# Board_R1.net
KiCad netlist of a schematic drawn in EAGLE
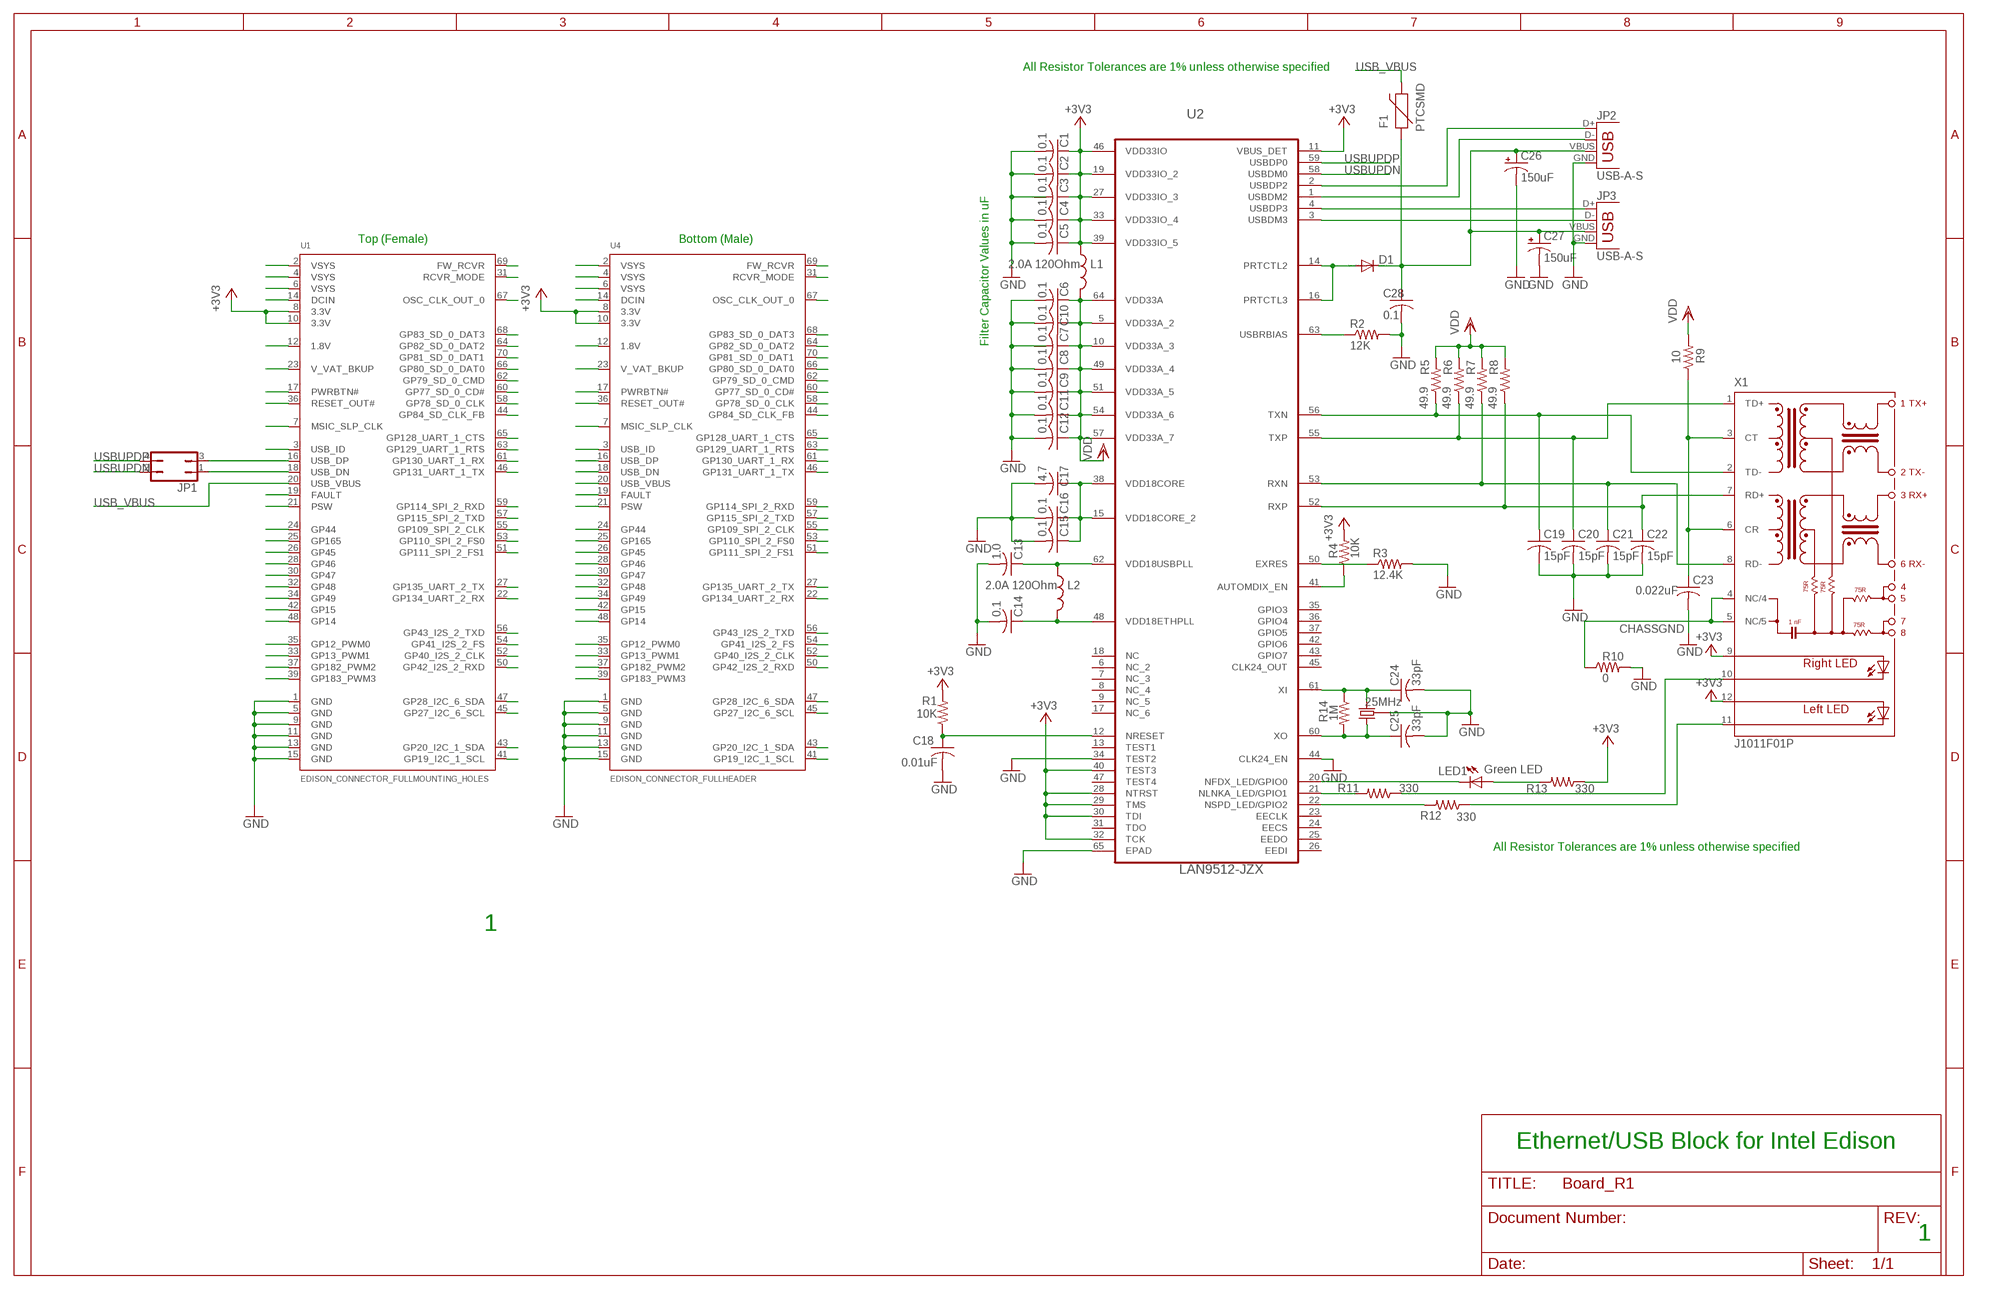
[diagram p0: schematic, sheet 1]

(export (version "E")
  (design (tool "Eeschema 10.0.6"))
  (components
    (comp (ref "C1")
      (value "0.1")
      (footprint "eagle-import:C0402K")
      (libsource (lib "eagle-import") (part "C-USC0402K"))
    )
    (comp (ref "C2")
      (value "0.1")
      (footprint "eagle-import:C0402K")
      (libsource (lib "eagle-import") (part "C-USC0402K"))
    )
    (comp (ref "C3")
      (value "0.1")
      (footprint "eagle-import:C0402K")
      (libsource (lib "eagle-import") (part "C-USC0402K"))
    )
    (comp (ref "C4")
      (value "0.1")
      (footprint "eagle-import:C0402K")
      (libsource (lib "eagle-import") (part "C-USC0402K"))
    )
    (comp (ref "C5")
      (value "0.1")
      (footprint "eagle-import:C0402K")
      (libsource (lib "eagle-import") (part "C-USC0402K"))
    )
    (comp (ref "C6")
      (value "0.1")
      (footprint "eagle-import:C0402K")
      (libsource (lib "eagle-import") (part "C-USC0402K"))
    )
    (comp (ref "C7")
      (value "0.1")
      (footprint "eagle-import:C0402K")
      (libsource (lib "eagle-import") (part "C-USC0402K"))
    )
    (comp (ref "C8")
      (value "0.1")
      (footprint "eagle-import:C0402K")
      (libsource (lib "eagle-import") (part "C-USC0402K"))
    )
    (comp (ref "C9")
      (value "0.1")
      (footprint "eagle-import:C0402K")
      (libsource (lib "eagle-import") (part "C-USC0402K"))
    )
    (comp (ref "C10")
      (value "0.1")
      (footprint "eagle-import:C0402K")
      (libsource (lib "eagle-import") (part "C-USC0402K"))
    )
    (comp (ref "C11")
      (value "0.1")
      (footprint "eagle-import:C0402K")
      (libsource (lib "eagle-import") (part "C-USC0402K"))
    )
    (comp (ref "C12")
      (value "0.1")
      (footprint "eagle-import:C0402K")
      (libsource (lib "eagle-import") (part "C-USC0402K"))
    )
    (comp (ref "C13")
      (value "1.0")
      (footprint "eagle-import:C0402K")
      (libsource (lib "eagle-import") (part "C-USC0402K"))
    )
    (comp (ref "C14")
      (value "0.1")
      (footprint "eagle-import:C0402K")
      (libsource (lib "eagle-import") (part "C-USC0402K"))
    )
    (comp (ref "C15")
      (value "0.1")
      (footprint "eagle-import:C0402K")
      (libsource (lib "eagle-import") (part "C-USC0402K"))
    )
    (comp (ref "C16")
      (value "0.1")
      (footprint "eagle-import:C0402K")
      (libsource (lib "eagle-import") (part "C-USC0402K"))
    )
    (comp (ref "C17")
      (value "4.7")
      (footprint "eagle-import:C0603K")
      (libsource (lib "eagle-import") (part "C-USC0603K"))
    )
    (comp (ref "C18")
      (value "0.01uF")
      (footprint "eagle-import:C0603K")
      (libsource (lib "eagle-import") (part "C-USC0603K"))
    )
    (comp (ref "C19")
      (value "15pF")
      (footprint "eagle-import:C0402")
      (libsource (lib "eagle-import") (part "C-USC0402"))
    )
    (comp (ref "C20")
      (value "15pF")
      (footprint "eagle-import:C0402")
      (libsource (lib "eagle-import") (part "C-USC0402"))
    )
    (comp (ref "C21")
      (value "15pF")
      (footprint "eagle-import:C0402")
      (libsource (lib "eagle-import") (part "C-USC0402"))
    )
    (comp (ref "C22")
      (value "15pF")
      (footprint "eagle-import:C0402")
      (libsource (lib "eagle-import") (part "C-USC0402"))
    )
    (comp (ref "C23")
      (value "0.022uF")
      (footprint "eagle-import:C0805")
      (libsource (lib "eagle-import") (part "resistor_C-USC0805"))
    )
    (comp (ref "C24")
      (value "33pF")
      (footprint "eagle-import:C0402")
      (libsource (lib "eagle-import") (part "C-USC0402"))
    )
    (comp (ref "C25")
      (value "33pF")
      (footprint "eagle-import:C0402")
      (libsource (lib "eagle-import") (part "C-USC0402"))
    )
    (comp (ref "C26")
      (value "150uF")
      (footprint "eagle-import:PANASONIC_E")
      (libsource (lib "eagle-import") (part "CAP_POLE"))
    )
    (comp (ref "C27")
      (value "150uF")
      (footprint "eagle-import:PANASONIC_E")
      (libsource (lib "eagle-import") (part "CAP_POLE"))
    )
    (comp (ref "C28")
      (value "0.1")
      (footprint "eagle-import:C0402K")
      (libsource (lib "eagle-import") (part "C-USC0402K"))
    )
    (comp (ref "D1")
      (value "DIODE-SOD123")
      (footprint "eagle-import:SOD123")
      (libsource (lib "eagle-import") (part "DIODE-SOD123"))
    )
    (comp (ref "F1")
      (value "PTCSMD")
      (footprint "eagle-import:PTC-1206")
      (libsource (lib "eagle-import") (part "PTCSMD"))
    )
    (comp (ref "JP1")
      (value "JP2Q")
      (footprint "eagle-import:JP2Q")
      (libsource (lib "eagle-import") (part "JP2Q"))
    )
    (comp (ref "JP2")
      (value "USB-A-S")
      (footprint "eagle-import:USB-A-S")
      (libsource (lib "eagle-import") (part "USB-A-S"))
    )
    (comp (ref "JP3")
      (value "USB-A-S")
      (footprint "eagle-import:USB-A-S")
      (libsource (lib "eagle-import") (part "USB-A-S"))
    )
    (comp (ref "L1")
      (value "2.0A 120Ohm")
      (footprint "eagle-import:L0603")
      (libsource (lib "eagle-import") (part "L-US0603"))
    )
    (comp (ref "L2")
      (value "2.0A 120Ohm")
      (footprint "eagle-import:L0603")
      (libsource (lib "eagle-import") (part "L-US0603"))
    )
    (comp (ref "LED1")
      (value "Green LED")
      (footprint "eagle-import:CHIP-LED0805")
      (libsource (lib "eagle-import") (part "LEDCHIP-LED0805"))
    )
    (comp (ref "R1")
      (value "10K")
      (footprint "eagle-import:R0603")
      (libsource (lib "eagle-import") (part "R-US_R0603"))
    )
    (comp (ref "R2")
      (value "12K")
      (footprint "eagle-import:R0603")
      (libsource (lib "eagle-import") (part "R-US_R0603"))
    )
    (comp (ref "R3")
      (value "12.4K")
      (footprint "eagle-import:R0603")
      (libsource (lib "eagle-import") (part "R-US_R0603"))
    )
    (comp (ref "R4")
      (value "10K")
      (footprint "eagle-import:R0603")
      (libsource (lib "eagle-import") (part "R-US_R0603"))
    )
    (comp (ref "R5")
      (value "49.9")
      (footprint "eagle-import:R0402")
      (libsource (lib "eagle-import") (part "R-US_R0402"))
    )
    (comp (ref "R6")
      (value "49.9")
      (footprint "eagle-import:R0402")
      (libsource (lib "eagle-import") (part "R-US_R0402"))
    )
    (comp (ref "R7")
      (value "49.9")
      (footprint "eagle-import:R0402")
      (libsource (lib "eagle-import") (part "R-US_R0402"))
    )
    (comp (ref "R8")
      (value "49.9")
      (footprint "eagle-import:R0402")
      (libsource (lib "eagle-import") (part "R-US_R0402"))
    )
    (comp (ref "R9")
      (value "10")
      (footprint "eagle-import:R0402")
      (libsource (lib "eagle-import") (part "R-US_R0402"))
    )
    (comp (ref "R10")
      (value "0")
      (footprint "eagle-import:R1210")
      (libsource (lib "eagle-import") (part "R-US_R1210"))
    )
    (comp (ref "R11")
      (value "330")
      (footprint "eagle-import:R0402")
      (libsource (lib "eagle-import") (part "R-US_R0402"))
    )
    (comp (ref "R12")
      (value "330")
      (footprint "eagle-import:R0402")
      (libsource (lib "eagle-import") (part "R-US_R0402"))
    )
    (comp (ref "R13")
      (value "330")
      (footprint "eagle-import:R0402")
      (libsource (lib "eagle-import") (part "R-US_R0402"))
    )
    (comp (ref "R14")
      (value "1M")
      (footprint "eagle-import:R0402")
      (libsource (lib "eagle-import") (part "R-US_R0402"))
    )
    (comp (ref "U$1")
      (value "25MHz")
      (footprint "eagle-import:CRYSTAL-SMD-5X3")
      (libsource (lib "eagle-import") (part "CRYSTAL-GROUNDED"))
    )
    (comp (ref "U1")
      (value "EDISON_CONNECTOR_FULLMOUNTING_HOLES")
      (footprint "eagle-import:EDISON_DAUGHTER")
      (libsource (lib "eagle-import") (part "EDISON_CONNECTOR_FULLMOUNTING_HOLES"))
    )
    (comp (ref "U2")
      (value "LAN9512-JZX")
      (footprint "eagle-import:QFN50P900X900X100-65N")
      (libsource (lib "eagle-import") (part "LAN9512-JZX"))
    )
    (comp (ref "U4")
      (value "EDISON_CONNECTOR_FULLHEADER")
      (footprint "eagle-import:DF40C-70DP-0.4(51)")
      (libsource (lib "eagle-import") (part "EDISON_CONNECTOR_FULLHEADER"))
    )
    (comp (ref "X1")
      (value "J1011F01P")
      (footprint "eagle-import:J1")
      (libsource (lib "eagle-import") (part "J1011F01P"))
    )
  )
  (nets
    (net (code "1") (name "+3V3") (class "Default")
      (node (ref "C1") (pin "1") (pinfunction "1_1") (pintype "passive"))
      (node (ref "C2") (pin "1") (pinfunction "1_1") (pintype "passive"))
      (node (ref "C3") (pin "1") (pinfunction "1_1") (pintype "passive"))
      (node (ref "C4") (pin "1") (pinfunction "1_1") (pintype "passive"))
      (node (ref "C5") (pin "1") (pinfunction "1_1") (pintype "passive"))
      (node (ref "L1") (pin "1") (pinfunction "1_1") (pintype "passive"))
      (node (ref "R1") (pin "2") (pinfunction "2_2") (pintype "passive"))
      (node (ref "R13") (pin "1") (pinfunction "1_1") (pintype "passive"))
      (node (ref "R4") (pin "2") (pinfunction "2_2") (pintype "passive"))
      (node (ref "U1") (pin "10") (pinfunction "3.3V_10") (pintype "bidirectional"))
      (node (ref "U1") (pin "8") (pinfunction "3.3V_8") (pintype "bidirectional"))
      (node (ref "U2") (pin "11") (pinfunction "VBUS_DET_11") (pintype "power_in"))
      (node (ref "U2") (pin "19") (pinfunction "VDD33IO_2_19") (pintype "power_in"))
      (node (ref "U2") (pin "27") (pinfunction "VDD33IO_3_27") (pintype "power_in"))
      (node (ref "U2") (pin "28") (pinfunction "NTRST_28") (pintype "passive"))
      (node (ref "U2") (pin "29") (pinfunction "TMS_29") (pintype "passive"))
      (node (ref "U2") (pin "30") (pinfunction "TDI_30") (pintype "passive"))
      (node (ref "U2") (pin "32") (pinfunction "TCK_32") (pintype "passive"))
      (node (ref "U2") (pin "33") (pinfunction "VDD33IO_4_33") (pintype "power_in"))
      (node (ref "U2") (pin "39") (pinfunction "VDD33IO_5_39") (pintype "power_in"))
      (node (ref "U2") (pin "40") (pinfunction "TEST3_40") (pintype "passive"))
      (node (ref "U2") (pin "46") (pinfunction "VDD33IO_46") (pintype "power_in"))
      (node (ref "U4") (pin "10") (pinfunction "3.3V_10") (pintype "bidirectional"))
      (node (ref "U4") (pin "8") (pinfunction "3.3V_8") (pintype "bidirectional"))
      (node (ref "X1") (pin "12") (pinfunction "AL_12") (pintype "passive"))
      (node (ref "X1") (pin "9") (pinfunction "A-R_9") (pintype "passive"))
    )
    (net (code "2") (name "/CHASSGND") (class "Default")
      (node (ref "R10") (pin "1") (pinfunction "1_1") (pintype "passive"))
      (node (ref "X1") (pin "4") (pinfunction "NC/4_4") (pintype "input"))
      (node (ref "X1") (pin "5") (pinfunction "NC/5_5") (pintype "input"))
    )
    (net (code "3") (name "/P2") (class "Default")
      (node (ref "U1") (pin "2") (pinfunction "VSYS_2") (pintype "bidirectional"))
      (node (ref "U4") (pin "2") (pinfunction "VSYS_2") (pintype "bidirectional"))
    )
    (net (code "4") (name "/P3") (class "Default")
      (node (ref "U1") (pin "3") (pinfunction "USB_ID_3") (pintype "bidirectional"))
      (node (ref "U4") (pin "3") (pinfunction "USB_ID_3") (pintype "bidirectional"))
    )
    (net (code "5") (name "/P4") (class "Default")
      (node (ref "U1") (pin "4") (pinfunction "VSYS_4") (pintype "bidirectional"))
      (node (ref "U4") (pin "4") (pinfunction "VSYS_4") (pintype "bidirectional"))
    )
    (net (code "6") (name "/P6") (class "Default")
      (node (ref "U1") (pin "6") (pinfunction "VSYS_6") (pintype "bidirectional"))
      (node (ref "U4") (pin "6") (pinfunction "VSYS_6") (pintype "bidirectional"))
    )
    (net (code "7") (name "/P7") (class "Default")
      (node (ref "U1") (pin "7") (pinfunction "MSIC_SLP_CLK_7") (pintype "bidirectional"))
      (node (ref "U4") (pin "7") (pinfunction "MSIC_SLP_CLK_7") (pintype "bidirectional"))
    )
    (net (code "8") (name "/P12") (class "Default")
      (node (ref "U1") (pin "12") (pinfunction "1.8V_12") (pintype "bidirectional"))
      (node (ref "U4") (pin "12") (pinfunction "1.8V_12") (pintype "bidirectional"))
    )
    (net (code "9") (name "/P14") (class "Default")
      (node (ref "U1") (pin "14") (pinfunction "DCIN_14") (pintype "bidirectional"))
      (node (ref "U4") (pin "14") (pinfunction "DCIN_14") (pintype "bidirectional"))
    )
    (net (code "10") (name "/P17") (class "Default")
      (node (ref "U1") (pin "17") (pinfunction "PWRBTN#_17") (pintype "bidirectional"))
      (node (ref "U4") (pin "17") (pinfunction "PWRBTN#_17") (pintype "bidirectional"))
    )
    (net (code "11") (name "/P19") (class "Default")
      (node (ref "U1") (pin "19") (pinfunction "FAULT_19") (pintype "bidirectional"))
      (node (ref "U4") (pin "19") (pinfunction "FAULT_19") (pintype "bidirectional"))
    )
    (net (code "12") (name "/P21") (class "Default")
      (node (ref "U1") (pin "21") (pinfunction "PSW_21") (pintype "bidirectional"))
      (node (ref "U4") (pin "21") (pinfunction "PSW_21") (pintype "bidirectional"))
    )
    (net (code "13") (name "/P22") (class "Default")
      (node (ref "U1") (pin "22") (pinfunction "GP134_UART_2_RX_22") (pintype "bidirectional"))
      (node (ref "U4") (pin "22") (pinfunction "GP134_UART_2_RX_22") (pintype "bidirectional"))
    )
    (net (code "14") (name "/P23") (class "Default")
      (node (ref "U1") (pin "23") (pinfunction "V_VAT_BKUP_23") (pintype "bidirectional"))
      (node (ref "U4") (pin "23") (pinfunction "V_VAT_BKUP_23") (pintype "bidirectional"))
    )
    (net (code "15") (name "/P24") (class "Default")
      (node (ref "U1") (pin "24") (pinfunction "GP44_24") (pintype "bidirectional"))
      (node (ref "U4") (pin "24") (pinfunction "GP44_24") (pintype "bidirectional"))
    )
    (net (code "16") (name "/P25") (class "Default")
      (node (ref "U1") (pin "25") (pinfunction "GP165_25") (pintype "bidirectional"))
      (node (ref "U4") (pin "25") (pinfunction "GP165_25") (pintype "bidirectional"))
    )
    (net (code "17") (name "/P26") (class "Default")
      (node (ref "U1") (pin "26") (pinfunction "GP45_26") (pintype "bidirectional"))
      (node (ref "U4") (pin "26") (pinfunction "GP45_26") (pintype "bidirectional"))
    )
    (net (code "18") (name "/P27") (class "Default")
      (node (ref "U1") (pin "27") (pinfunction "GP135_UART_2_TX_27") (pintype "bidirectional"))
      (node (ref "U4") (pin "27") (pinfunction "GP135_UART_2_TX_27") (pintype "bidirectional"))
    )
    (net (code "19") (name "/P28") (class "Default")
      (node (ref "U1") (pin "28") (pinfunction "GP46_28") (pintype "bidirectional"))
      (node (ref "U4") (pin "28") (pinfunction "GP46_28") (pintype "bidirectional"))
    )
    (net (code "20") (name "/P30") (class "Default")
      (node (ref "U1") (pin "30") (pinfunction "GP47_30") (pintype "bidirectional"))
      (node (ref "U4") (pin "30") (pinfunction "GP47_30") (pintype "bidirectional"))
    )
    (net (code "21") (name "/P31") (class "Default")
      (node (ref "U1") (pin "31") (pinfunction "RCVR_MODE_31") (pintype "bidirectional"))
      (node (ref "U4") (pin "31") (pinfunction "RCVR_MODE_31") (pintype "bidirectional"))
    )
    (net (code "22") (name "/P32") (class "Default")
      (node (ref "U1") (pin "32") (pinfunction "GP48_32") (pintype "bidirectional"))
      (node (ref "U4") (pin "32") (pinfunction "GP48_32") (pintype "bidirectional"))
    )
    (net (code "23") (name "/P33") (class "Default")
      (node (ref "U1") (pin "33") (pinfunction "GP13_PWM1_33") (pintype "bidirectional"))
      (node (ref "U4") (pin "33") (pinfunction "GP13_PWM1_33") (pintype "bidirectional"))
    )
    (net (code "24") (name "/P34") (class "Default")
      (node (ref "U1") (pin "34") (pinfunction "GP49_34") (pintype "bidirectional"))
      (node (ref "U4") (pin "34") (pinfunction "GP49_34") (pintype "bidirectional"))
    )
    (net (code "25") (name "/P35") (class "Default")
      (node (ref "U1") (pin "35") (pinfunction "GP12_PWM0_35") (pintype "bidirectional"))
      (node (ref "U4") (pin "35") (pinfunction "GP12_PWM0_35") (pintype "bidirectional"))
    )
    (net (code "26") (name "/P36") (class "Default")
      (node (ref "U1") (pin "36") (pinfunction "RESET_OUT#_36") (pintype "bidirectional"))
      (node (ref "U4") (pin "36") (pinfunction "RESET_OUT#_36") (pintype "bidirectional"))
    )
    (net (code "27") (name "/P37") (class "Default")
      (node (ref "U1") (pin "37") (pinfunction "GP182_PWM2_37") (pintype "bidirectional"))
      (node (ref "U4") (pin "37") (pinfunction "GP182_PWM2_37") (pintype "bidirectional"))
    )
    (net (code "28") (name "/P39") (class "Default")
      (node (ref "U1") (pin "39") (pinfunction "GP183_PWM3_39") (pintype "bidirectional"))
      (node (ref "U4") (pin "39") (pinfunction "GP183_PWM3_39") (pintype "bidirectional"))
    )
    (net (code "29") (name "/P41") (class "Default")
      (node (ref "U1") (pin "41") (pinfunction "GP19_I2C_1_SCL_41") (pintype "bidirectional"))
      (node (ref "U4") (pin "41") (pinfunction "GP19_I2C_1_SCL_41") (pintype "bidirectional"))
    )
    (net (code "30") (name "/P42") (class "Default")
      (node (ref "U1") (pin "42") (pinfunction "GP15_42") (pintype "bidirectional"))
      (node (ref "U4") (pin "42") (pinfunction "GP15_42") (pintype "bidirectional"))
    )
    (net (code "31") (name "/P43") (class "Default")
      (node (ref "U1") (pin "43") (pinfunction "GP20_I2C_1_SDA_43") (pintype "bidirectional"))
      (node (ref "U4") (pin "43") (pinfunction "GP20_I2C_1_SDA_43") (pintype "bidirectional"))
    )
    (net (code "32") (name "/P44") (class "Default")
      (node (ref "U1") (pin "44") (pinfunction "GP84_SD_CLK_FB_44") (pintype "bidirectional"))
      (node (ref "U4") (pin "44") (pinfunction "GP84_SD_CLK_FB_44") (pintype "bidirectional"))
    )
    (net (code "33") (name "/P45") (class "Default")
      (node (ref "U1") (pin "45") (pinfunction "GP27_I2C_6_SCL_45") (pintype "bidirectional"))
      (node (ref "U4") (pin "45") (pinfunction "GP27_I2C_6_SCL_45") (pintype "bidirectional"))
    )
    (net (code "34") (name "/P46") (class "Default")
      (node (ref "U1") (pin "46") (pinfunction "GP131_UART_1_TX_46") (pintype "bidirectional"))
      (node (ref "U4") (pin "46") (pinfunction "GP131_UART_1_TX_46") (pintype "bidirectional"))
    )
    (net (code "35") (name "/P47") (class "Default")
      (node (ref "U1") (pin "47") (pinfunction "GP28_I2C_6_SDA_47") (pintype "bidirectional"))
      (node (ref "U4") (pin "47") (pinfunction "GP28_I2C_6_SDA_47") (pintype "bidirectional"))
    )
    (net (code "36") (name "/P48") (class "Default")
      (node (ref "U1") (pin "48") (pinfunction "GP14_48") (pintype "bidirectional"))
      (node (ref "U4") (pin "48") (pinfunction "GP14_48") (pintype "bidirectional"))
    )
    (net (code "37") (name "/P50") (class "Default")
      (node (ref "U1") (pin "50") (pinfunction "GP42_I2S_2_RXD_50") (pintype "bidirectional"))
      (node (ref "U4") (pin "50") (pinfunction "GP42_I2S_2_RXD_50") (pintype "bidirectional"))
    )
    (net (code "38") (name "/P51") (class "Default")
      (node (ref "U1") (pin "51") (pinfunction "GP111_SPI_2_FS1_51") (pintype "bidirectional"))
      (node (ref "U4") (pin "51") (pinfunction "GP111_SPI_2_FS1_51") (pintype "bidirectional"))
    )
    (net (code "39") (name "/P52") (class "Default")
      (node (ref "U1") (pin "52") (pinfunction "GP40_I2S_2_CLK_52") (pintype "bidirectional"))
      (node (ref "U4") (pin "52") (pinfunction "GP40_I2S_2_CLK_52") (pintype "bidirectional"))
    )
    (net (code "40") (name "/P53") (class "Default")
      (node (ref "U1") (pin "53") (pinfunction "GP110_SPI_2_FS0_53") (pintype "bidirectional"))
      (node (ref "U4") (pin "53") (pinfunction "GP110_SPI_2_FS0_53") (pintype "bidirectional"))
    )
    (net (code "41") (name "/P54") (class "Default")
      (node (ref "U1") (pin "54") (pinfunction "GP41_I2S_2_FS_54") (pintype "bidirectional"))
      (node (ref "U4") (pin "54") (pinfunction "GP41_I2S_2_FS_54") (pintype "bidirectional"))
    )
    (net (code "42") (name "/P55") (class "Default")
      (node (ref "U1") (pin "55") (pinfunction "GP109_SPI_2_CLK_55") (pintype "bidirectional"))
      (node (ref "U4") (pin "55") (pinfunction "GP109_SPI_2_CLK_55") (pintype "bidirectional"))
    )
    (net (code "43") (name "/P56") (class "Default")
      (node (ref "U1") (pin "56") (pinfunction "GP43_I2S_2_TXD_56") (pintype "bidirectional"))
      (node (ref "U4") (pin "56") (pinfunction "GP43_I2S_2_TXD_56") (pintype "bidirectional"))
    )
    (net (code "44") (name "/P57") (class "Default")
      (node (ref "U1") (pin "57") (pinfunction "GP115_SPI_2_TXD_57") (pintype "bidirectional"))
      (node (ref "U4") (pin "57") (pinfunction "GP115_SPI_2_TXD_57") (pintype "bidirectional"))
    )
    (net (code "45") (name "/P58") (class "Default")
      (node (ref "U1") (pin "58") (pinfunction "GP78_SD_0_CLK_58") (pintype "bidirectional"))
      (node (ref "U4") (pin "58") (pinfunction "GP78_SD_0_CLK_58") (pintype "bidirectional"))
    )
    (net (code "46") (name "/P59") (class "Default")
      (node (ref "U1") (pin "59") (pinfunction "GP114_SPI_2_RXD_59") (pintype "bidirectional"))
      (node (ref "U4") (pin "59") (pinfunction "GP114_SPI_2_RXD_59") (pintype "bidirectional"))
    )
    (net (code "47") (name "/P60") (class "Default")
      (node (ref "U1") (pin "60") (pinfunction "GP77_SD_0_CD#_60") (pintype "bidirectional"))
      (node (ref "U4") (pin "60") (pinfunction "GP77_SD_0_CD#_60") (pintype "bidirectional"))
    )
    (net (code "48") (name "/P61") (class "Default")
      (node (ref "U1") (pin "61") (pinfunction "GP130_UART_1_RX_61") (pintype "bidirectional"))
      (node (ref "U4") (pin "61") (pinfunction "GP130_UART_1_RX_61") (pintype "bidirectional"))
    )
    (net (code "49") (name "/P62") (class "Default")
      (node (ref "U1") (pin "62") (pinfunction "GP79_SD_0_CMD_62") (pintype "bidirectional"))
      (node (ref "U4") (pin "62") (pinfunction "GP79_SD_0_CMD_62") (pintype "bidirectional"))
    )
    (net (code "50") (name "/P63") (class "Default")
      (node (ref "U1") (pin "63") (pinfunction "GP129_UART_1_RTS_63") (pintype "bidirectional"))
      (node (ref "U4") (pin "63") (pinfunction "GP129_UART_1_RTS_63") (pintype "bidirectional"))
    )
    (net (code "51") (name "/P64") (class "Default")
      (node (ref "U1") (pin "64") (pinfunction "GP82_SD_0_DAT2_64") (pintype "bidirectional"))
      (node (ref "U4") (pin "64") (pinfunction "GP82_SD_0_DAT2_64") (pintype "bidirectional"))
    )
    (net (code "52") (name "/P65") (class "Default")
      (node (ref "U1") (pin "65") (pinfunction "GP128_UART_1_CTS_65") (pintype "bidirectional"))
      (node (ref "U4") (pin "65") (pinfunction "GP128_UART_1_CTS_65") (pintype "bidirectional"))
    )
    (net (code "53") (name "/P66") (class "Default")
      (node (ref "U1") (pin "66") (pinfunction "GP80_SD_0_DAT0_66") (pintype "bidirectional"))
      (node (ref "U4") (pin "66") (pinfunction "GP80_SD_0_DAT0_66") (pintype "bidirectional"))
    )
    (net (code "54") (name "/P67") (class "Default")
      (node (ref "U1") (pin "67") (pinfunction "OSC_CLK_OUT_0_67") (pintype "bidirectional"))
      (node (ref "U4") (pin "67") (pinfunction "OSC_CLK_OUT_0_67") (pintype "bidirectional"))
    )
    (net (code "55") (name "/P68") (class "Default")
      (node (ref "U1") (pin "68") (pinfunction "GP83_SD_0_DAT3_68") (pintype "bidirectional"))
      (node (ref "U4") (pin "68") (pinfunction "GP83_SD_0_DAT3_68") (pintype "bidirectional"))
    )
    (net (code "56") (name "/P69") (class "Default")
      (node (ref "U1") (pin "69") (pinfunction "FW_RCVR_69") (pintype "bidirectional"))
      (node (ref "U4") (pin "69") (pinfunction "FW_RCVR_69") (pintype "bidirectional"))
    )
    (net (code "57") (name "/P70") (class "Default")
      (node (ref "U1") (pin "70") (pinfunction "GP81_SD_0_DAT1_70") (pintype "bidirectional"))
      (node (ref "U4") (pin "70") (pinfunction "GP81_SD_0_DAT1_70") (pintype "bidirectional"))
    )
    (net (code "58") (name "/USBUP") (class "Default")
      (node (ref "JP1") (pin "3") (pinfunction "3_3") (pintype "passive"))
      (node (ref "U1") (pin "16") (pinfunction "USB_DP_16") (pintype "bidirectional"))
      (node (ref "U4") (pin "16") (pinfunction "USB_DP_16") (pintype "bidirectional"))
    )
    (net (code "59") (name "/USBUP2") (class "Default")
      (node (ref "JP1") (pin "1") (pinfunction "1_1") (pintype "passive"))
      (node (ref "U1") (pin "18") (pinfunction "USB_DN_18") (pintype "bidirectional"))
      (node (ref "U4") (pin "18") (pinfunction "USB_DN_18") (pintype "bidirectional"))
    )
    (net (code "60") (name "/USBUPDN") (class "Default")
      (node (ref "JP1") (pin "2") (pinfunction "2_2") (pintype "passive"))
      (node (ref "U2") (pin "58") (pinfunction "USBDM0_58") (pintype "passive"))
    )
    (net (code "61") (name "/USBUPDP") (class "Default")
      (node (ref "JP1") (pin "4") (pinfunction "4_4") (pintype "passive"))
      (node (ref "U2") (pin "59") (pinfunction "USBDP0_59") (pintype "passive"))
    )
    (net (code "62") (name "/USB_VBUS") (class "Default")
      (node (ref "F1") (pin "2") (pinfunction "2_2") (pintype "bidirectional"))
      (node (ref "U1") (pin "20") (pinfunction "USB_VBUS_20") (pintype "bidirectional"))
      (node (ref "U4") (pin "20") (pinfunction "USB_VBUS_20") (pintype "bidirectional"))
    )
    (net (code "63") (name "GND") (class "Default")
      (node (ref "C1") (pin "2") (pinfunction "2_2") (pintype "passive"))
      (node (ref "C10") (pin "2") (pinfunction "2_2") (pintype "passive"))
      (node (ref "C11") (pin "2") (pinfunction "2_2") (pintype "passive"))
      (node (ref "C12") (pin "2") (pinfunction "2_2") (pintype "passive"))
      (node (ref "C13") (pin "2") (pinfunction "2_2") (pintype "passive"))
      (node (ref "C14") (pin "2") (pinfunction "2_2") (pintype "passive"))
      (node (ref "C15") (pin "2") (pinfunction "2_2") (pintype "passive"))
      (node (ref "C16") (pin "2") (pinfunction "2_2") (pintype "passive"))
      (node (ref "C17") (pin "2") (pinfunction "2_2") (pintype "passive"))
      (node (ref "C18") (pin "2") (pinfunction "2_2") (pintype "passive"))
      (node (ref "C19") (pin "2") (pinfunction "2_2") (pintype "passive"))
      (node (ref "C2") (pin "2") (pinfunction "2_2") (pintype "passive"))
      (node (ref "C20") (pin "2") (pinfunction "2_2") (pintype "passive"))
      (node (ref "C21") (pin "2") (pinfunction "2_2") (pintype "passive"))
      (node (ref "C22") (pin "2") (pinfunction "2_2") (pintype "passive"))
      (node (ref "C23") (pin "2") (pinfunction "2_2") (pintype "passive"))
      (node (ref "C24") (pin "2") (pinfunction "2_2") (pintype "passive"))
      (node (ref "C25") (pin "2") (pinfunction "2_2") (pintype "passive"))
      (node (ref "C26") (pin "-") (pinfunction "-_-") (pintype "passive"))
      (node (ref "C27") (pin "-") (pinfunction "-_-") (pintype "passive"))
      (node (ref "C28") (pin "2") (pinfunction "2_2") (pintype "passive"))
      (node (ref "C3") (pin "2") (pinfunction "2_2") (pintype "passive"))
      (node (ref "C4") (pin "2") (pinfunction "2_2") (pintype "passive"))
      (node (ref "C5") (pin "2") (pinfunction "2_2") (pintype "passive"))
      (node (ref "C6") (pin "2") (pinfunction "2_2") (pintype "passive"))
      (node (ref "C7") (pin "2") (pinfunction "2_2") (pintype "passive"))
      (node (ref "C8") (pin "2") (pinfunction "2_2") (pintype "passive"))
      (node (ref "C9") (pin "2") (pinfunction "2_2") (pintype "passive"))
      (node (ref "JP2") (pin "GND") (pinfunction "GND_GND") (pintype "bidirectional"))
      (node (ref "JP3") (pin "GND") (pinfunction "GND_GND") (pintype "bidirectional"))
      (node (ref "R10") (pin "2") (pinfunction "2_2") (pintype "passive"))
      (node (ref "R2") (pin "2") (pinfunction "2_2") (pintype "passive"))
      (node (ref "R3") (pin "2") (pinfunction "2_2") (pintype "passive"))
      (node (ref "U$1") (pin "2") (pinfunction "3_2") (pintype "passive"))
      (node (ref "U$1") (pin "4") (pinfunction "3_4") (pintype "passive"))
      (node (ref "U1") (pin "1") (pinfunction "GND_1") (pintype "bidirectional"))
      (node (ref "U1") (pin "11") (pinfunction "GND_11") (pintype "bidirectional"))
      (node (ref "U1") (pin "13") (pinfunction "GND_13") (pintype "bidirectional"))
      (node (ref "U1") (pin "15") (pinfunction "GND_15") (pintype "bidirectional"))
      (node (ref "U1") (pin "5") (pinfunction "GND_5") (pintype "bidirectional"))
      (node (ref "U1") (pin "9") (pinfunction "GND_9") (pintype "bidirectional"))
      (node (ref "U2") (pin "34") (pinfunction "TEST2_34") (pintype "passive"))
      (node (ref "U2") (pin "44") (pinfunction "CLK24_EN_44") (pintype "passive"))
      (node (ref "U2") (pin "65") (pinfunction "EPAD_65") (pintype "passive"))
      (node (ref "U4") (pin "1") (pinfunction "GND_1") (pintype "bidirectional"))
      (node (ref "U4") (pin "11") (pinfunction "GND_11") (pintype "bidirectional"))
      (node (ref "U4") (pin "13") (pinfunction "GND_13") (pintype "bidirectional"))
      (node (ref "U4") (pin "15") (pinfunction "GND_15") (pintype "bidirectional"))
      (node (ref "U4") (pin "5") (pinfunction "GND_5") (pintype "bidirectional"))
      (node (ref "U4") (pin "9") (pinfunction "GND_9") (pintype "bidirectional"))
    )
    (net (code "64") (name "Net-(C26-Pad+)") (class "Default")
      (node (ref "C26") (pin "+") (pinfunction "+_+") (pintype "passive"))
      (node (ref "C27") (pin "+") (pinfunction "+_+") (pintype "passive"))
      (node (ref "C28") (pin "1") (pinfunction "1_1") (pintype "passive"))
      (node (ref "D1") (pin "C") (pinfunction "C_C") (pintype "passive"))
      (node (ref "F1") (pin "1") (pinfunction "1_1") (pintype "bidirectional"))
      (node (ref "JP2") (pin "VBUS") (pinfunction "VBUS_VBUS") (pintype "bidirectional"))
      (node (ref "JP3") (pin "VBUS") (pinfunction "VBUS_VBUS") (pintype "bidirectional"))
    )
    (net (code "65") (name "Net-(LED1-PadA)") (class "Default")
      (node (ref "LED1") (pin "A") (pinfunction "A_A") (pintype "passive"))
      (node (ref "R13") (pin "2") (pinfunction "2_2") (pintype "passive"))
    )
    (net (code "66") (name "Net-(U$1-1)") (class "Default")
      (node (ref "C25") (pin "1") (pinfunction "1_1") (pintype "passive"))
      (node (ref "R14") (pin "2") (pinfunction "2_2") (pintype "passive"))
      (node (ref "U$1") (pin "3") (pinfunction "1_3") (pintype "passive"))
      (node (ref "U2") (pin "60") (pinfunction "XO_60") (pintype "passive"))
    )
    (net (code "67") (name "Net-(U$1-2)") (class "Default")
      (node (ref "C24") (pin "1") (pinfunction "1_1") (pintype "passive"))
      (node (ref "R14") (pin "1") (pinfunction "1_1") (pintype "passive"))
      (node (ref "U$1") (pin "1") (pinfunction "2_1") (pintype "passive"))
      (node (ref "U2") (pin "61") (pinfunction "XI_61") (pintype "passive"))
    )
    (net (code "68") (name "Net-(U2-AUTOMDIX_EN)") (class "Default")
      (node (ref "R4") (pin "1") (pinfunction "1_1") (pintype "passive"))
      (node (ref "U2") (pin "41") (pinfunction "AUTOMDIX_EN_41") (pintype "passive"))
    )
    (net (code "69") (name "Net-(U2-EXRES)") (class "Default")
      (node (ref "R3") (pin "1") (pinfunction "1_1") (pintype "passive"))
      (node (ref "U2") (pin "50") (pinfunction "EXRES_50") (pintype "passive"))
    )
    (net (code "70") (name "Net-(U2-NFDX_LED{slash}GPIO0)") (class "Default")
      (node (ref "LED1") (pin "C") (pinfunction "C_C") (pintype "passive"))
      (node (ref "U2") (pin "20") (pinfunction "NFDX_LED/GPIO0_20") (pintype "bidirectional"))
    )
    (net (code "71") (name "Net-(U2-NLNKA_LED{slash}GPIO1)") (class "Default")
      (node (ref "R11") (pin "2") (pinfunction "2_2") (pintype "passive"))
      (node (ref "U2") (pin "21") (pinfunction "NLNKA_LED/GPIO1_21") (pintype "bidirectional"))
    )
    (net (code "72") (name "Net-(U2-NRESET)") (class "Default")
      (node (ref "C18") (pin "1") (pinfunction "1_1") (pintype "passive"))
      (node (ref "R1") (pin "1") (pinfunction "1_1") (pintype "passive"))
      (node (ref "U2") (pin "12") (pinfunction "NRESET_12") (pintype "passive"))
    )
    (net (code "73") (name "Net-(U2-NSPD_LED{slash}GPIO2)") (class "Default")
      (node (ref "R12") (pin "2") (pinfunction "2_2") (pintype "passive"))
      (node (ref "U2") (pin "22") (pinfunction "NSPD_LED/GPIO2_22") (pintype "bidirectional"))
    )
    (net (code "74") (name "Net-(U2-PRTCTL2)") (class "Default")
      (node (ref "D1") (pin "A") (pinfunction "A_A") (pintype "passive"))
      (node (ref "U2") (pin "14") (pinfunction "PRTCTL2_14") (pintype "passive"))
      (node (ref "U2") (pin "16") (pinfunction "PRTCTL3_16") (pintype "passive"))
    )
    (net (code "75") (name "Net-(U2-RXN)") (class "Default")
      (node (ref "C21") (pin "1") (pinfunction "1_1") (pintype "passive"))
      (node (ref "R7") (pin "1") (pinfunction "1_1") (pintype "passive"))
      (node (ref "U2") (pin "53") (pinfunction "RXN_53") (pintype "passive"))
      (node (ref "X1") (pin "8") (pinfunction "RD-_8") (pintype "input"))
    )
    (net (code "76") (name "Net-(U2-RXP)") (class "Default")
      (node (ref "C22") (pin "1") (pinfunction "1_1") (pintype "passive"))
      (node (ref "R8") (pin "1") (pinfunction "1_1") (pintype "passive"))
      (node (ref "U2") (pin "52") (pinfunction "RXP_52") (pintype "passive"))
      (node (ref "X1") (pin "7") (pinfunction "RD+_7") (pintype "input"))
    )
    (net (code "77") (name "Net-(U2-TXN)") (class "Default")
      (node (ref "C19") (pin "1") (pinfunction "1_1") (pintype "passive"))
      (node (ref "R5") (pin "1") (pinfunction "1_1") (pintype "passive"))
      (node (ref "U2") (pin "56") (pinfunction "TXN_56") (pintype "passive"))
      (node (ref "X1") (pin "2") (pinfunction "TD-_2") (pintype "input"))
    )
    (net (code "78") (name "Net-(U2-TXP)") (class "Default")
      (node (ref "C20") (pin "1") (pinfunction "1_1") (pintype "passive"))
      (node (ref "R6") (pin "1") (pinfunction "1_1") (pintype "passive"))
      (node (ref "U2") (pin "55") (pinfunction "TXP_55") (pintype "passive"))
      (node (ref "X1") (pin "1") (pinfunction "TD+_1") (pintype "input"))
    )
    (net (code "79") (name "Net-(U2-USBDM2)") (class "Default")
      (node (ref "JP2") (pin "D-") (pinfunction "D-_D-") (pintype "bidirectional"))
      (node (ref "U2") (pin "1") (pinfunction "USBDM2_1") (pintype "passive"))
    )
    (net (code "80") (name "Net-(U2-USBDM3)") (class "Default")
      (node (ref "JP3") (pin "D-") (pinfunction "D-_D-") (pintype "bidirectional"))
      (node (ref "U2") (pin "3") (pinfunction "USBDM3_3") (pintype "passive"))
    )
    (net (code "81") (name "Net-(U2-USBDP2)") (class "Default")
      (node (ref "JP2") (pin "D+") (pinfunction "D+_D+") (pintype "bidirectional"))
      (node (ref "U2") (pin "2") (pinfunction "USBDP2_2") (pintype "passive"))
    )
    (net (code "82") (name "Net-(U2-USBDP3)") (class "Default")
      (node (ref "JP3") (pin "D+") (pinfunction "D+_D+") (pintype "bidirectional"))
      (node (ref "U2") (pin "4") (pinfunction "USBDP3_4") (pintype "passive"))
    )
    (net (code "83") (name "Net-(U2-USBRBIAS)") (class "Default")
      (node (ref "R2") (pin "1") (pinfunction "1_1") (pintype "passive"))
      (node (ref "U2") (pin "63") (pinfunction "USBRBIAS_63") (pintype "passive"))
    )
    (net (code "84") (name "Net-(U2-VDD18CORE)") (class "Default")
      (node (ref "C15") (pin "1") (pinfunction "1_1") (pintype "passive"))
      (node (ref "C16") (pin "1") (pinfunction "1_1") (pintype "passive"))
      (node (ref "C17") (pin "1") (pinfunction "1_1") (pintype "passive"))
      (node (ref "U2") (pin "15") (pinfunction "VDD18CORE_2_15") (pintype "power_in"))
      (node (ref "U2") (pin "38") (pinfunction "VDD18CORE_38") (pintype "power_in"))
    )
    (net (code "85") (name "Net-(U2-VDD18ETHPLL)") (class "Default")
      (node (ref "C14") (pin "1") (pinfunction "1_1") (pintype "passive"))
      (node (ref "L2") (pin "2") (pinfunction "2_2") (pintype "passive"))
      (node (ref "U2") (pin "48") (pinfunction "VDD18ETHPLL_48") (pintype "power_in"))
    )
    (net (code "86") (name "Net-(U2-VDD18USBPLL)") (class "Default")
      (node (ref "C13") (pin "1") (pinfunction "1_1") (pintype "passive"))
      (node (ref "L2") (pin "1") (pinfunction "1_1") (pintype "passive"))
      (node (ref "U2") (pin "62") (pinfunction "VDD18USBPLL_62") (pintype "power_in"))
    )
    (net (code "87") (name "Net-(X1-C-L)") (class "Default")
      (node (ref "R12") (pin "1") (pinfunction "1_1") (pintype "passive"))
      (node (ref "X1") (pin "11") (pinfunction "C-L_11") (pintype "passive"))
    )
    (net (code "88") (name "Net-(X1-C-R)") (class "Default")
      (node (ref "R11") (pin "1") (pinfunction "1_1") (pintype "passive"))
      (node (ref "X1") (pin "10") (pinfunction "C-R_10") (pintype "passive"))
    )
    (net (code "89") (name "Net-(X1-CR)") (class "Default")
      (node (ref "C23") (pin "1") (pinfunction "1_1") (pintype "passive"))
      (node (ref "R9") (pin "1") (pinfunction "1_1") (pintype "passive"))
      (node (ref "X1") (pin "3") (pinfunction "CT_3") (pintype "input"))
      (node (ref "X1") (pin "6") (pinfunction "CR_6") (pintype "input"))
    )
    (net (code "90") (name "VDD") (class "Default")
      (node (ref "C10") (pin "1") (pinfunction "1_1") (pintype "passive"))
      (node (ref "C11") (pin "1") (pinfunction "1_1") (pintype "passive"))
      (node (ref "C12") (pin "1") (pinfunction "1_1") (pintype "passive"))
      (node (ref "C6") (pin "1") (pinfunction "1_1") (pintype "passive"))
      (node (ref "C7") (pin "1") (pinfunction "1_1") (pintype "passive"))
      (node (ref "C8") (pin "1") (pinfunction "1_1") (pintype "passive"))
      (node (ref "C9") (pin "1") (pinfunction "1_1") (pintype "passive"))
      (node (ref "L1") (pin "2") (pinfunction "2_2") (pintype "passive"))
      (node (ref "R5") (pin "2") (pinfunction "2_2") (pintype "passive"))
      (node (ref "R6") (pin "2") (pinfunction "2_2") (pintype "passive"))
      (node (ref "R7") (pin "2") (pinfunction "2_2") (pintype "passive"))
      (node (ref "R8") (pin "2") (pinfunction "2_2") (pintype "passive"))
      (node (ref "R9") (pin "2") (pinfunction "2_2") (pintype "passive"))
      (node (ref "U2") (pin "10") (pinfunction "VDD33A_3_10") (pintype "power_in"))
      (node (ref "U2") (pin "49") (pinfunction "VDD33A_4_49") (pintype "power_in"))
      (node (ref "U2") (pin "5") (pinfunction "VDD33A_2_5") (pintype "power_in"))
      (node (ref "U2") (pin "51") (pinfunction "VDD33A_5_51") (pintype "power_in"))
      (node (ref "U2") (pin "54") (pinfunction "VDD33A_6_54") (pintype "power_in"))
      (node (ref "U2") (pin "57") (pinfunction "VDD33A_7_57") (pintype "power_in"))
      (node (ref "U2") (pin "64") (pinfunction "VDD33A_64") (pintype "power_in"))
    )
    (net (code "91") (name "unconnected-(U2-CLK24_OUT-Pad45)") (class "Default")
      (node (ref "U2") (pin "45") (pinfunction "CLK24_OUT_45") (pintype "passive"))
    )
    (net (code "92") (name "unconnected-(U2-EECLK-Pad23)") (class "Default")
      (node (ref "U2") (pin "23") (pinfunction "EECLK_23") (pintype "passive"))
    )
    (net (code "93") (name "unconnected-(U2-EECS-Pad24)") (class "Default")
      (node (ref "U2") (pin "24") (pinfunction "EECS_24") (pintype "passive"))
    )
    (net (code "94") (name "unconnected-(U2-EEDI-Pad26)") (class "Default")
      (node (ref "U2") (pin "26") (pinfunction "EEDI_26") (pintype "passive"))
    )
    (net (code "95") (name "unconnected-(U2-EEDO-Pad25)") (class "Default")
      (node (ref "U2") (pin "25") (pinfunction "EEDO_25") (pintype "passive"))
    )
    (net (code "96") (name "unconnected-(U2-GPIO3-Pad35)") (class "Default")
      (node (ref "U2") (pin "35") (pinfunction "GPIO3_35") (pintype "bidirectional"))
    )
    (net (code "97") (name "unconnected-(U2-GPIO4-Pad36)") (class "Default")
      (node (ref "U2") (pin "36") (pinfunction "GPIO4_36") (pintype "bidirectional"))
    )
    (net (code "98") (name "unconnected-(U2-GPIO5-Pad37)") (class "Default")
      (node (ref "U2") (pin "37") (pinfunction "GPIO5_37") (pintype "bidirectional"))
    )
    (net (code "99") (name "unconnected-(U2-GPIO6-Pad42)") (class "Default")
      (node (ref "U2") (pin "42") (pinfunction "GPIO6_42") (pintype "bidirectional"))
    )
    (net (code "100") (name "unconnected-(U2-GPIO7-Pad43)") (class "Default")
      (node (ref "U2") (pin "43") (pinfunction "GPIO7_43") (pintype "bidirectional"))
    )
    (net (code "101") (name "unconnected-(U2-NC-Pad18)") (class "Default")
      (node (ref "U2") (pin "18") (pinfunction "NC_18") (pintype "no_connect"))
    )
    (net (code "102") (name "unconnected-(U2-NC_2-Pad6)") (class "Default")
      (node (ref "U2") (pin "6") (pinfunction "NC_2_6") (pintype "no_connect"))
    )
    (net (code "103") (name "unconnected-(U2-NC_3-Pad7)") (class "Default")
      (node (ref "U2") (pin "7") (pinfunction "NC_3_7") (pintype "no_connect"))
    )
    (net (code "104") (name "unconnected-(U2-NC_4-Pad8)") (class "Default")
      (node (ref "U2") (pin "8") (pinfunction "NC_4_8") (pintype "no_connect"))
    )
    (net (code "105") (name "unconnected-(U2-NC_5-Pad9)") (class "Default")
      (node (ref "U2") (pin "9") (pinfunction "NC_5_9") (pintype "no_connect"))
    )
    (net (code "106") (name "unconnected-(U2-NC_6-Pad17)") (class "Default")
      (node (ref "U2") (pin "17") (pinfunction "NC_6_17") (pintype "no_connect"))
    )
    (net (code "107") (name "unconnected-(U2-TDO-Pad31)") (class "Default")
      (node (ref "U2") (pin "31") (pinfunction "TDO_31") (pintype "passive"))
    )
    (net (code "108") (name "unconnected-(U2-TEST1-Pad13)") (class "Default")
      (node (ref "U2") (pin "13") (pinfunction "TEST1_13") (pintype "passive"))
    )
    (net (code "109") (name "unconnected-(U2-TEST4-Pad47)") (class "Default")
      (node (ref "U2") (pin "47") (pinfunction "TEST4_47") (pintype "passive"))
    )
  )
)
